# 220V_Sense_Input_Socket.net
KiCad netlist of a schematic drawn in Altium Designer
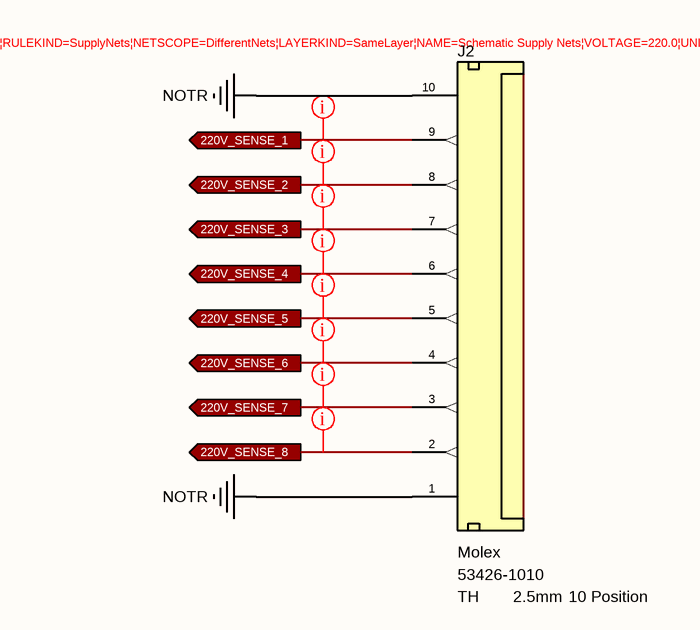
[diagram p0: 220V Sense Input Socket.SchDoc]

(export (version "E")
  (design (tool "Eeschema 10.0.6"))
  (components
    (comp (ref "J2")
      (value "53426-1010")
      (footprint "Connector 10P (2.54)")
      (description "2.50mm Pitch Mini-Lock Wire-to-Board Header Right Angle Friction and Positive Lock 10 Circuits")
      (fields
        (field (name "MANUFACTURER NAME") "Molex")
        (field (name "MANUFACTURER PART NUMBER") "53426-1010")
        (field (name "CASE") "TH")
        (field (name "PITCH") "2.5mm")
        (field (name "POSITION") "10 Position")
      )
      (libsource (lib "Akkoyun") (part "Connector - Tunic 10P (2.5)"))
    )
  )
  (nets
    (net (code "1") (name "/220V_SENSE_1") (class "Default")
      (node (ref "J2") (pin "9") (pinfunction "Pin-9_9") (pintype "output"))
    )
    (net (code "2") (name "/220V_SENSE_2") (class "Default")
      (node (ref "J2") (pin "8") (pinfunction "Pin-8_8") (pintype "output"))
    )
    (net (code "3") (name "/220V_SENSE_3") (class "Default")
      (node (ref "J2") (pin "7") (pinfunction "Pin-7_7") (pintype "output"))
    )
    (net (code "4") (name "/220V_SENSE_4") (class "Default")
      (node (ref "J2") (pin "6") (pinfunction "Pin-6_6") (pintype "output"))
    )
    (net (code "5") (name "/220V_SENSE_5") (class "Default")
      (node (ref "J2") (pin "5") (pinfunction "Pin-5_5") (pintype "output"))
    )
    (net (code "6") (name "/220V_SENSE_6") (class "Default")
      (node (ref "J2") (pin "4") (pinfunction "Pin-4_4") (pintype "output"))
    )
    (net (code "7") (name "/220V_SENSE_7") (class "Default")
      (node (ref "J2") (pin "3") (pinfunction "Pin-3_3") (pintype "output"))
    )
    (net (code "8") (name "/220V_SENSE_8") (class "Default")
      (node (ref "J2") (pin "2") (pinfunction "Pin-2_2") (pintype "output"))
    )
    (net (code "9") (name "NOTR") (class "Default")
      (node (ref "J2") (pin "1") (pinfunction "Pin-1_1") (pintype "passive"))
      (node (ref "J2") (pin "10") (pinfunction "Pin-10_10") (pintype "passive"))
    )
  )
)
